# 19_SOLEDNOID_2.net
KiCad netlist of a schematic drawn in Altium Designer
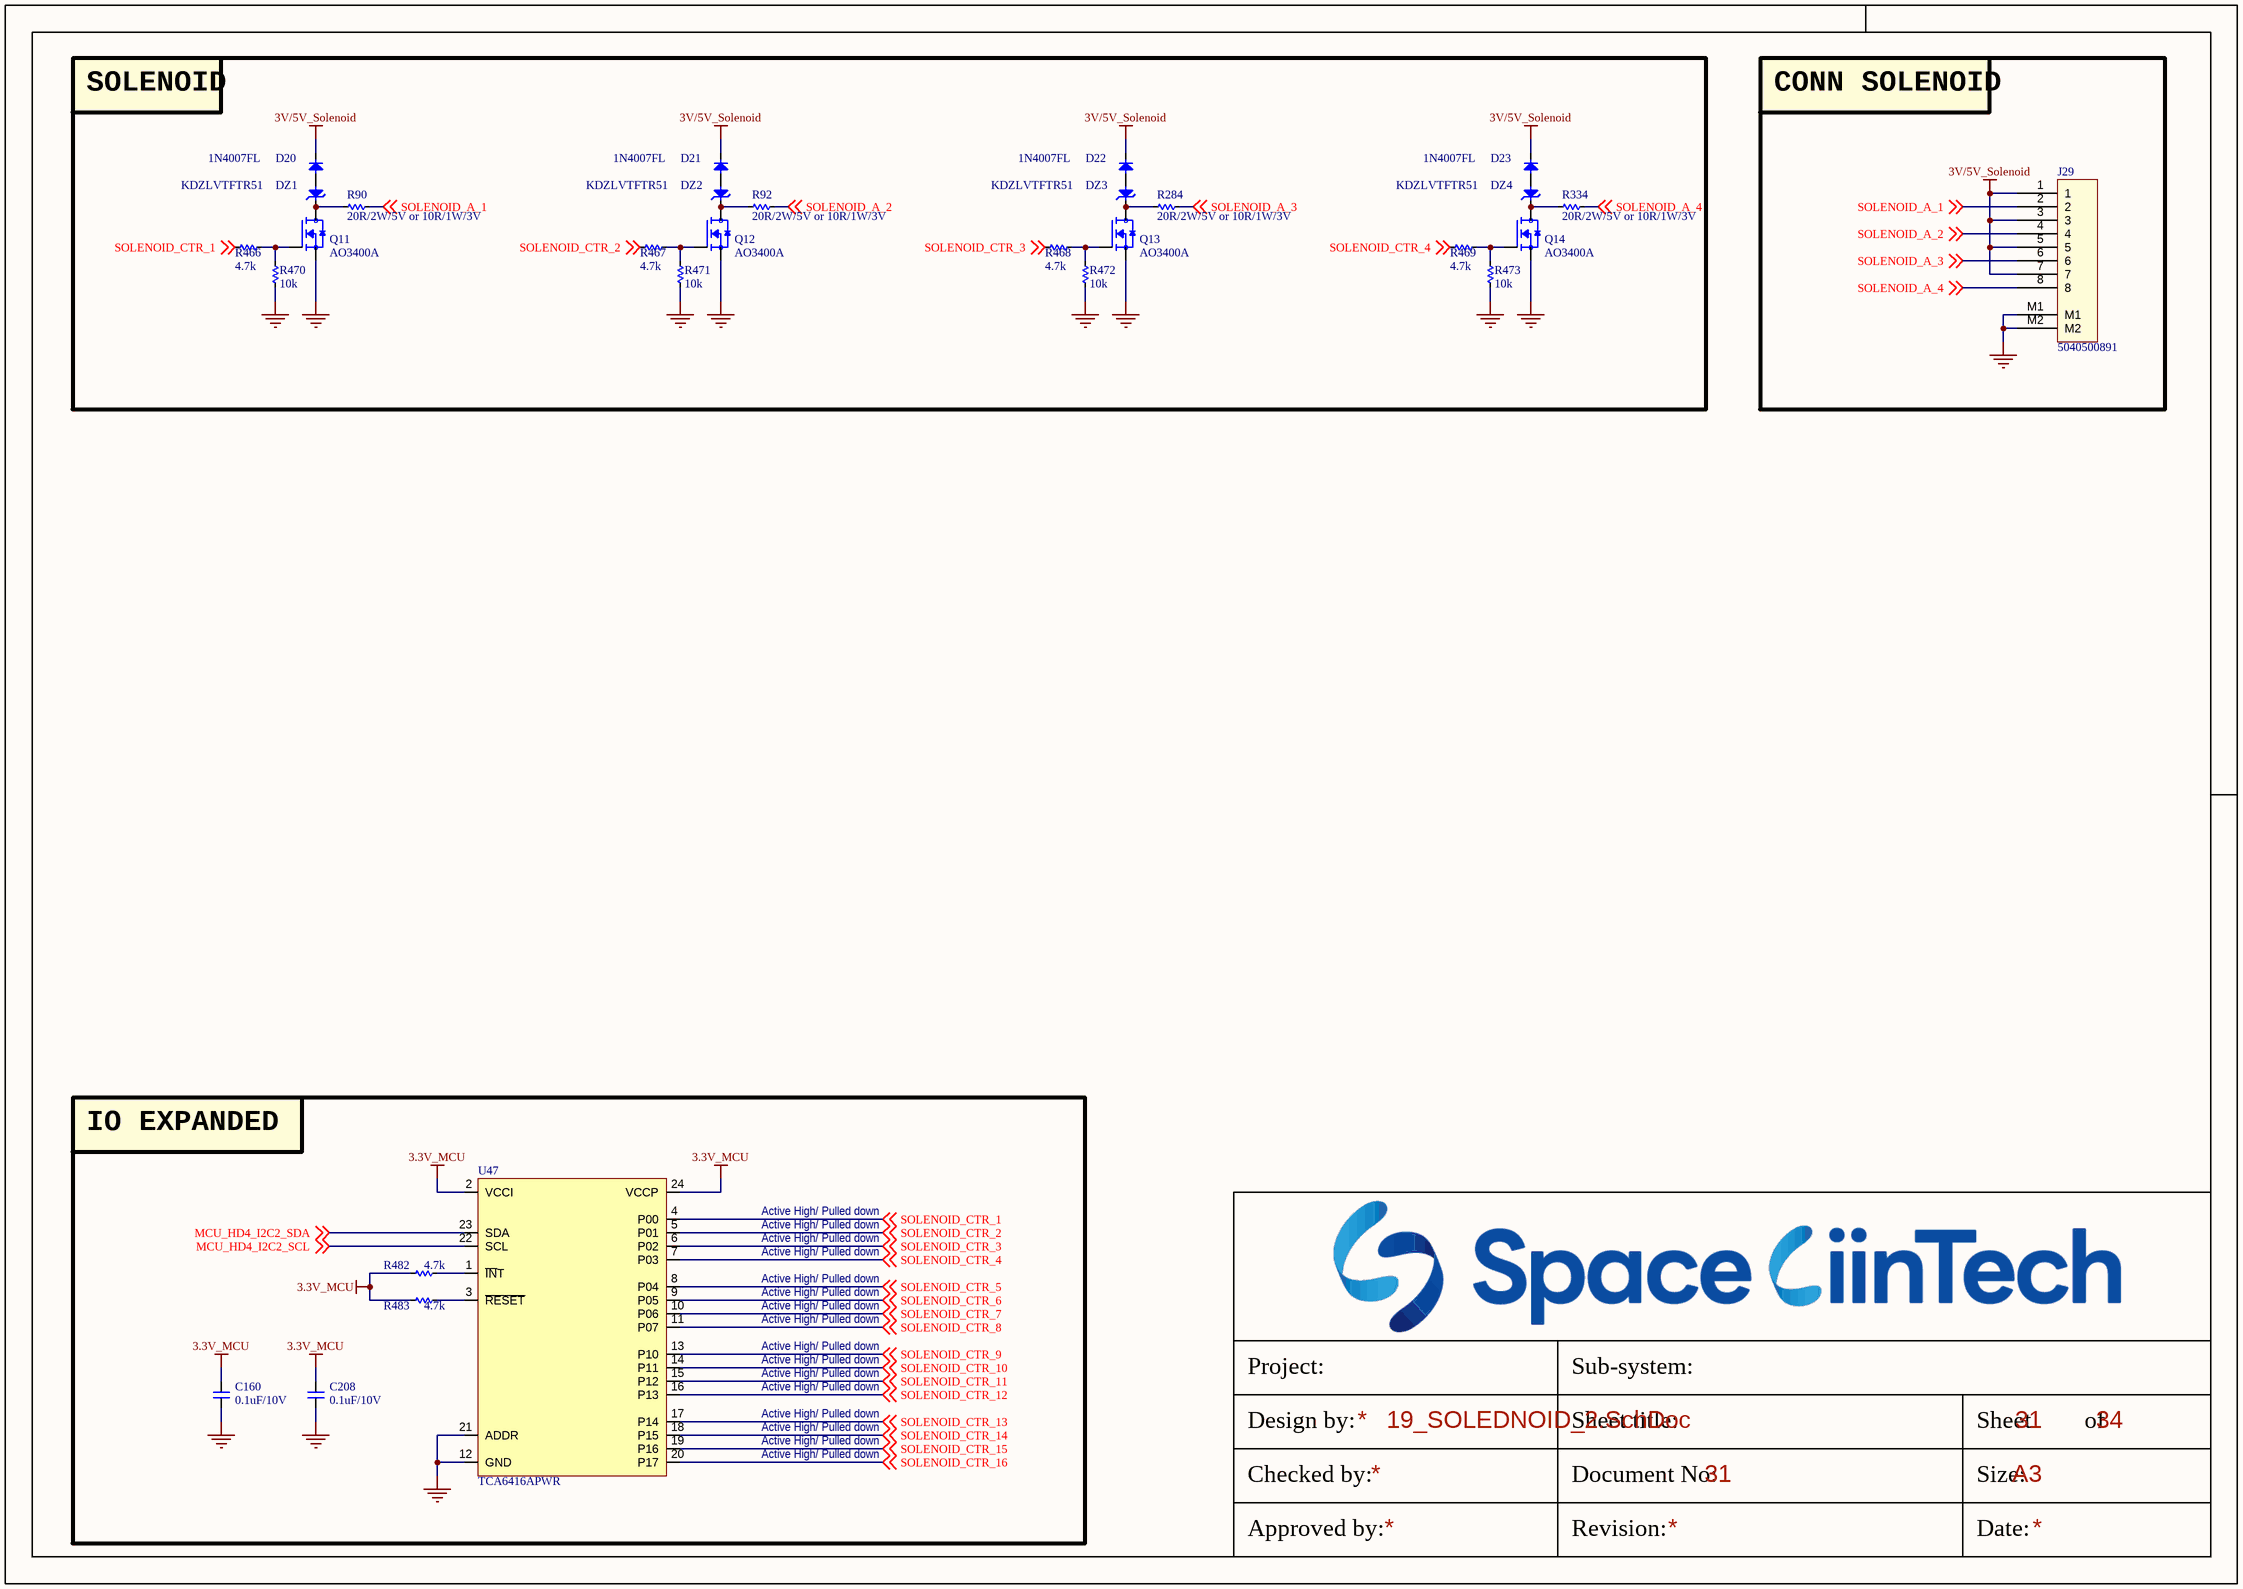
[diagram p0: 19_SOLEDNOID_2.SchDoc]

(export (version "E")
  (design (tool "Eeschema 10.0.6"))
  (components
    (comp (ref "C160")
      (value "0.1uF/10V")
      (footprint "CAP_C_1005X50_L")
      (description "CAP")
      (libsource (lib "LABLIB") (part "_CAP_C_2"))
    )
    (comp (ref "C208")
      (value "0.1uF/10V")
      (footprint "CAP_C_1005X50_L")
      (description "CAP")
      (libsource (lib "LABLIB") (part "_CAP_C_2"))
    )
    (comp (ref "D20")
      (value "1N4007FL")
      (footprint "SOD3717X145N")
      (description "Default Diode")
      (fields (field (name "PUBLISHER") "Altium Limited"))
      (libsource (lib "LABLIB") (part "Diode SMD"))
    )
    (comp (ref "D21")
      (value "1N4007FL")
      (footprint "SOD3717X145N")
      (description "Default Diode")
      (fields (field (name "PUBLISHER") "Altium Limited"))
      (libsource (lib "LABLIB") (part "Diode SMD"))
    )
    (comp (ref "D22")
      (value "1N4007FL")
      (footprint "SOD3717X145N")
      (description "Default Diode")
      (fields (field (name "PUBLISHER") "Altium Limited"))
      (libsource (lib "LABLIB") (part "Diode SMD"))
    )
    (comp (ref "D23")
      (value "1N4007FL")
      (footprint "SOD3717X145N")
      (description "Default Diode")
      (fields (field (name "PUBLISHER") "Altium Limited"))
      (libsource (lib "LABLIB") (part "Diode SMD"))
    )
    (comp (ref "DZ1")
      (value "KDZLVTFTR51")
      (footprint "SOD3717X145N")
      (description "Zenner")
      (libsource (lib "LABLIB") (part "DIODE Zener"))
    )
    (comp (ref "DZ2")
      (value "KDZLVTFTR51")
      (footprint "SOD3717X145N")
      (description "Zenner")
      (libsource (lib "LABLIB") (part "DIODE Zener"))
    )
    (comp (ref "DZ3")
      (value "KDZLVTFTR51")
      (footprint "SOD3717X145N")
      (description "Zenner")
      (libsource (lib "LABLIB") (part "DIODE Zener"))
    )
    (comp (ref "DZ4")
      (value "KDZLVTFTR51")
      (footprint "SOD3717X145N")
      (description "Zenner")
      (libsource (lib "LABLIB") (part "DIODE Zener"))
    )
    (comp (ref "J29")
      (value "5040500891")
      (footprint "MOLEX_5040500891")
      (libsource (lib "LABLIB") (part "Header 8x1_2M"))
    )
    (comp (ref "Q11")
      (value "AO3400A")
      (footprint "SOT95P240X120-3N")
      (description "N-Channel 30 V 5.7A (Ta) 1.4W (Ta) Surface Mount SOT-23-3")
      (fields (field (name "MF") "Alpha & Omega Semiconductor"))
      (libsource (lib "LABLIB") (part "MOSFET_N"))
    )
    (comp (ref "Q12")
      (value "AO3400A")
      (footprint "SOT95P240X120-3N")
      (description "N-Channel 30 V 5.7A (Ta) 1.4W (Ta) Surface Mount SOT-23-3")
      (fields (field (name "MF") "Alpha & Omega Semiconductor"))
      (libsource (lib "LABLIB") (part "MOSFET_N"))
    )
    (comp (ref "Q13")
      (value "AO3400A")
      (footprint "SOT95P240X120-3N")
      (description "N-Channel 30 V 5.7A (Ta) 1.4W (Ta) Surface Mount SOT-23-3")
      (fields (field (name "MF") "Alpha & Omega Semiconductor"))
      (libsource (lib "LABLIB") (part "MOSFET_N"))
    )
    (comp (ref "Q14")
      (value "AO3400A")
      (footprint "SOT95P240X120-3N")
      (description "N-Channel 30 V 5.7A (Ta) 1.4W (Ta) Surface Mount SOT-23-3")
      (fields (field (name "MF") "Alpha & Omega Semiconductor"))
      (libsource (lib "LABLIB") (part "MOSFET_N"))
    )
    (comp (ref "R90")
      (value "20R/2W/5V or 10R/1W/3V")
      (footprint "RES_C_6331X65_N")
      (description "RES")
      (libsource (lib "LABLIB") (part "_RES_B_2"))
    )
    (comp (ref "R92")
      (value "20R/2W/5V or 10R/1W/3V")
      (footprint "RES_C_6331X65_N")
      (description "RES")
      (libsource (lib "LABLIB") (part "_RES_B_2"))
    )
    (comp (ref "R284")
      (value "20R/2W/5V or 10R/1W/3V")
      (footprint "RES_C_6331X65_N")
      (description "RES")
      (libsource (lib "LABLIB") (part "_RES_B_2"))
    )
    (comp (ref "R334")
      (value "20R/2W/5V or 10R/1W/3V")
      (footprint "RES_C_6331X65_N")
      (description "RES")
      (libsource (lib "LABLIB") (part "_RES_B_2"))
    )
    (comp (ref "R466")
      (value "4.7k")
      (footprint "RES_C_1005x30_L")
      (description "RES")
      (libsource (lib "LABLIB") (part "_RES_B_2"))
    )
    (comp (ref "R467")
      (value "4.7k")
      (footprint "RES_C_1005x30_L")
      (description "RES")
      (libsource (lib "LABLIB") (part "_RES_B_2"))
    )
    (comp (ref "R468")
      (value "4.7k")
      (footprint "RES_C_1005x30_L")
      (description "RES")
      (libsource (lib "LABLIB") (part "_RES_B_2"))
    )
    (comp (ref "R469")
      (value "4.7k")
      (footprint "RES_C_1005x30_L")
      (description "RES")
      (libsource (lib "LABLIB") (part "_RES_B_2"))
    )
    (comp (ref "R470")
      (value "10k")
      (footprint "RES_C_1005x30_L")
      (description "RES")
      (libsource (lib "LABLIB") (part "_RES_B_2"))
    )
    (comp (ref "R471")
      (value "10k")
      (footprint "RES_C_1005x30_L")
      (description "RES")
      (libsource (lib "LABLIB") (part "_RES_B_2"))
    )
    (comp (ref "R472")
      (value "10k")
      (footprint "RES_C_1005x30_L")
      (description "RES")
      (libsource (lib "LABLIB") (part "_RES_B_2"))
    )
    (comp (ref "R473")
      (value "10k")
      (footprint "RES_C_1005x30_L")
      (description "RES")
      (libsource (lib "LABLIB") (part "_RES_B_2"))
    )
    (comp (ref "R482")
      (value "4.7k")
      (footprint "RES_C_1005x30_L")
      (description "RES")
      (libsource (lib "LABLIB") (part "_RES_B_2"))
    )
    (comp (ref "R483")
      (value "4.7k")
      (footprint "RES_C_1005x30_L")
      (description "RES")
      (libsource (lib "LABLIB") (part "_RES_B_2"))
    )
    (comp (ref "U47")
      (value "TCA6416APWR")
      (footprint "SOP65P440W-24N")
      (libsource (lib "CAMERA_SchLib") (part "IC_I2Cto16IO_TCA6416APWR"))
    )
  )
  (nets
    (net (code "1") (name "3.3V_MCU") (class "Default")
      (node (ref "C160") (pin "2") (pinfunction "2_2") (pintype "passive"))
      (node (ref "C208") (pin "2") (pinfunction "2_2") (pintype "passive"))
      (node (ref "R482") (pin "1") (pinfunction "1_1") (pintype "passive"))
      (node (ref "R483") (pin "1") (pinfunction "1_1") (pintype "passive"))
      (node (ref "U47") (pin "2") (pinfunction "VCCI_2") (pintype "passive"))
      (node (ref "U47") (pin "24") (pinfunction "VCCP_24") (pintype "passive"))
    )
    (net (code "2") (name "3V{slash}5V_Solenoid") (class "Default")
      (node (ref "D20") (pin "1") (pinfunction "K_1") (pintype "passive"))
      (node (ref "D21") (pin "1") (pinfunction "K_1") (pintype "passive"))
      (node (ref "D22") (pin "1") (pinfunction "K_1") (pintype "passive"))
      (node (ref "D23") (pin "1") (pinfunction "K_1") (pintype "passive"))
      (node (ref "J29") (pin "1") (pinfunction "1_1") (pintype "passive"))
      (node (ref "J29") (pin "3") (pinfunction "3_3") (pintype "passive"))
      (node (ref "J29") (pin "5") (pinfunction "5_5") (pintype "passive"))
      (node (ref "J29") (pin "7") (pinfunction "7_7") (pintype "passive"))
    )
    (net (code "3") (name "GND") (class "Default")
      (node (ref "C160") (pin "1") (pinfunction "1_1") (pintype "passive"))
      (node (ref "C208") (pin "1") (pinfunction "1_1") (pintype "passive"))
      (node (ref "J29") (pin "M1") (pinfunction "M1_M1") (pintype "passive"))
      (node (ref "J29") (pin "M2") (pinfunction "M2_M2") (pintype "passive"))
      (node (ref "Q11") (pin "2") (pinfunction "S_2") (pintype "passive"))
      (node (ref "Q12") (pin "2") (pinfunction "S_2") (pintype "passive"))
      (node (ref "Q13") (pin "2") (pinfunction "S_2") (pintype "passive"))
      (node (ref "Q14") (pin "2") (pinfunction "S_2") (pintype "passive"))
      (node (ref "R470") (pin "1") (pinfunction "1_1") (pintype "passive"))
      (node (ref "R471") (pin "1") (pinfunction "1_1") (pintype "passive"))
      (node (ref "R472") (pin "1") (pinfunction "1_1") (pintype "passive"))
      (node (ref "R473") (pin "1") (pinfunction "1_1") (pintype "passive"))
      (node (ref "U47") (pin "12") (pinfunction "GND_12") (pintype "passive"))
      (node (ref "U47") (pin "21") (pinfunction "ADDR_21") (pintype "passive"))
    )
    (net (code "4") (name "MCU_HD4_I2C2_SCL") (class "Default")
      (node (ref "U47") (pin "22") (pinfunction "SCL_22") (pintype "passive"))
    )
    (net (code "5") (name "MCU_HD4_I2C2_SDA") (class "Default")
      (node (ref "U47") (pin "23") (pinfunction "SDA_23") (pintype "passive"))
    )
    (net (code "6") (name "Net-(D20-A)") (class "Default")
      (node (ref "D20") (pin "2") (pinfunction "A_2") (pintype "passive"))
      (node (ref "DZ1") (pin "2") (pinfunction "A_2") (pintype "passive"))
    )
    (net (code "7") (name "Net-(D21-A)") (class "Default")
      (node (ref "D21") (pin "2") (pinfunction "A_2") (pintype "passive"))
      (node (ref "DZ2") (pin "2") (pinfunction "A_2") (pintype "passive"))
    )
    (net (code "8") (name "Net-(D22-A)") (class "Default")
      (node (ref "D22") (pin "2") (pinfunction "A_2") (pintype "passive"))
      (node (ref "DZ3") (pin "2") (pinfunction "A_2") (pintype "passive"))
    )
    (net (code "9") (name "Net-(D23-A)") (class "Default")
      (node (ref "D23") (pin "2") (pinfunction "A_2") (pintype "passive"))
      (node (ref "DZ4") (pin "2") (pinfunction "A_2") (pintype "passive"))
    )
    (net (code "10") (name "Net-(DZ1-K)") (class "Default")
      (node (ref "DZ1") (pin "1") (pinfunction "K_1") (pintype "passive"))
      (node (ref "Q11") (pin "3") (pinfunction "D_3") (pintype "passive"))
      (node (ref "R90") (pin "2") (pinfunction "2_2") (pintype "passive"))
    )
    (net (code "11") (name "Net-(DZ2-K)") (class "Default")
      (node (ref "DZ2") (pin "1") (pinfunction "K_1") (pintype "passive"))
      (node (ref "Q12") (pin "3") (pinfunction "D_3") (pintype "passive"))
      (node (ref "R92") (pin "2") (pinfunction "2_2") (pintype "passive"))
    )
    (net (code "12") (name "Net-(DZ3-K)") (class "Default")
      (node (ref "DZ3") (pin "1") (pinfunction "K_1") (pintype "passive"))
      (node (ref "Q13") (pin "3") (pinfunction "D_3") (pintype "passive"))
      (node (ref "R284") (pin "2") (pinfunction "2_2") (pintype "passive"))
    )
    (net (code "13") (name "Net-(DZ4-K)") (class "Default")
      (node (ref "DZ4") (pin "1") (pinfunction "K_1") (pintype "passive"))
      (node (ref "Q14") (pin "3") (pinfunction "D_3") (pintype "passive"))
      (node (ref "R334") (pin "2") (pinfunction "2_2") (pintype "passive"))
    )
    (net (code "14") (name "Net-(Q11-G)") (class "Default")
      (node (ref "Q11") (pin "1") (pinfunction "G_1") (pintype "passive"))
      (node (ref "R466") (pin "1") (pinfunction "1_1") (pintype "passive"))
      (node (ref "R470") (pin "2") (pinfunction "2_2") (pintype "passive"))
    )
    (net (code "15") (name "Net-(Q12-G)") (class "Default")
      (node (ref "Q12") (pin "1") (pinfunction "G_1") (pintype "passive"))
      (node (ref "R467") (pin "1") (pinfunction "1_1") (pintype "passive"))
      (node (ref "R471") (pin "2") (pinfunction "2_2") (pintype "passive"))
    )
    (net (code "16") (name "Net-(Q13-G)") (class "Default")
      (node (ref "Q13") (pin "1") (pinfunction "G_1") (pintype "passive"))
      (node (ref "R468") (pin "1") (pinfunction "1_1") (pintype "passive"))
      (node (ref "R472") (pin "2") (pinfunction "2_2") (pintype "passive"))
    )
    (net (code "17") (name "Net-(Q14-G)") (class "Default")
      (node (ref "Q14") (pin "1") (pinfunction "G_1") (pintype "passive"))
      (node (ref "R469") (pin "1") (pinfunction "1_1") (pintype "passive"))
      (node (ref "R473") (pin "2") (pinfunction "2_2") (pintype "passive"))
    )
    (net (code "18") (name "Net-(U47-~{IN}T)") (class "Default")
      (node (ref "R482") (pin "2") (pinfunction "2_2") (pintype "passive"))
      (node (ref "U47") (pin "1") (pinfunction "~{IN}T_1") (pintype "passive"))
    )
    (net (code "19") (name "Net-(U47-~{RESET})") (class "Default")
      (node (ref "R483") (pin "2") (pinfunction "2_2") (pintype "passive"))
      (node (ref "U47") (pin "3") (pinfunction "~{RESET}_3") (pintype "passive"))
    )
    (net (code "20") (name "SOLENOID_A_1") (class "Default")
      (node (ref "J29") (pin "2") (pinfunction "2_2") (pintype "passive"))
      (node (ref "R90") (pin "1") (pinfunction "1_1") (pintype "passive"))
    )
    (net (code "21") (name "SOLENOID_A_2") (class "Default")
      (node (ref "J29") (pin "4") (pinfunction "4_4") (pintype "passive"))
      (node (ref "R92") (pin "1") (pinfunction "1_1") (pintype "passive"))
    )
    (net (code "22") (name "SOLENOID_A_3") (class "Default")
      (node (ref "J29") (pin "6") (pinfunction "6_6") (pintype "passive"))
      (node (ref "R284") (pin "1") (pinfunction "1_1") (pintype "passive"))
    )
    (net (code "23") (name "SOLENOID_A_4") (class "Default")
      (node (ref "J29") (pin "8") (pinfunction "8_8") (pintype "passive"))
      (node (ref "R334") (pin "1") (pinfunction "1_1") (pintype "passive"))
    )
    (net (code "24") (name "SOLENOID_CTR_1") (class "Default")
      (node (ref "R466") (pin "2") (pinfunction "2_2") (pintype "passive"))
      (node (ref "U47") (pin "4") (pinfunction "P00_4") (pintype "passive"))
    )
    (net (code "25") (name "SOLENOID_CTR_2") (class "Default")
      (node (ref "R467") (pin "2") (pinfunction "2_2") (pintype "passive"))
      (node (ref "U47") (pin "5") (pinfunction "P01_5") (pintype "passive"))
    )
    (net (code "26") (name "SOLENOID_CTR_3") (class "Default")
      (node (ref "R468") (pin "2") (pinfunction "2_2") (pintype "passive"))
      (node (ref "U47") (pin "6") (pinfunction "P02_6") (pintype "passive"))
    )
    (net (code "27") (name "SOLENOID_CTR_4") (class "Default")
      (node (ref "R469") (pin "2") (pinfunction "2_2") (pintype "passive"))
      (node (ref "U47") (pin "7") (pinfunction "P03_7") (pintype "passive"))
    )
    (net (code "28") (name "SOLENOID_CTR_5") (class "Default")
      (node (ref "U47") (pin "8") (pinfunction "P04_8") (pintype "passive"))
    )
    (net (code "29") (name "SOLENOID_CTR_6") (class "Default")
      (node (ref "U47") (pin "9") (pinfunction "P05_9") (pintype "passive"))
    )
    (net (code "30") (name "SOLENOID_CTR_7") (class "Default")
      (node (ref "U47") (pin "10") (pinfunction "P06_10") (pintype "passive"))
    )
    (net (code "31") (name "SOLENOID_CTR_8") (class "Default")
      (node (ref "U47") (pin "11") (pinfunction "P07_11") (pintype "passive"))
    )
    (net (code "32") (name "SOLENOID_CTR_9") (class "Default")
      (node (ref "U47") (pin "13") (pinfunction "P10_13") (pintype "passive"))
    )
    (net (code "33") (name "SOLENOID_CTR_10") (class "Default")
      (node (ref "U47") (pin "14") (pinfunction "P11_14") (pintype "passive"))
    )
    (net (code "34") (name "SOLENOID_CTR_11") (class "Default")
      (node (ref "U47") (pin "15") (pinfunction "P12_15") (pintype "passive"))
    )
    (net (code "35") (name "SOLENOID_CTR_12") (class "Default")
      (node (ref "U47") (pin "16") (pinfunction "P13_16") (pintype "passive"))
    )
    (net (code "36") (name "SOLENOID_CTR_13") (class "Default")
      (node (ref "U47") (pin "17") (pinfunction "P14_17") (pintype "passive"))
    )
    (net (code "37") (name "SOLENOID_CTR_14") (class "Default")
      (node (ref "U47") (pin "18") (pinfunction "P15_18") (pintype "passive"))
    )
    (net (code "38") (name "SOLENOID_CTR_15") (class "Default")
      (node (ref "U47") (pin "19") (pinfunction "P16_19") (pintype "passive"))
    )
    (net (code "39") (name "SOLENOID_CTR_16") (class "Default")
      (node (ref "U47") (pin "20") (pinfunction "P17_20") (pintype "passive"))
    )
  )
)
